# LCD.net
KiCad netlist of a schematic drawn in Altium Designer
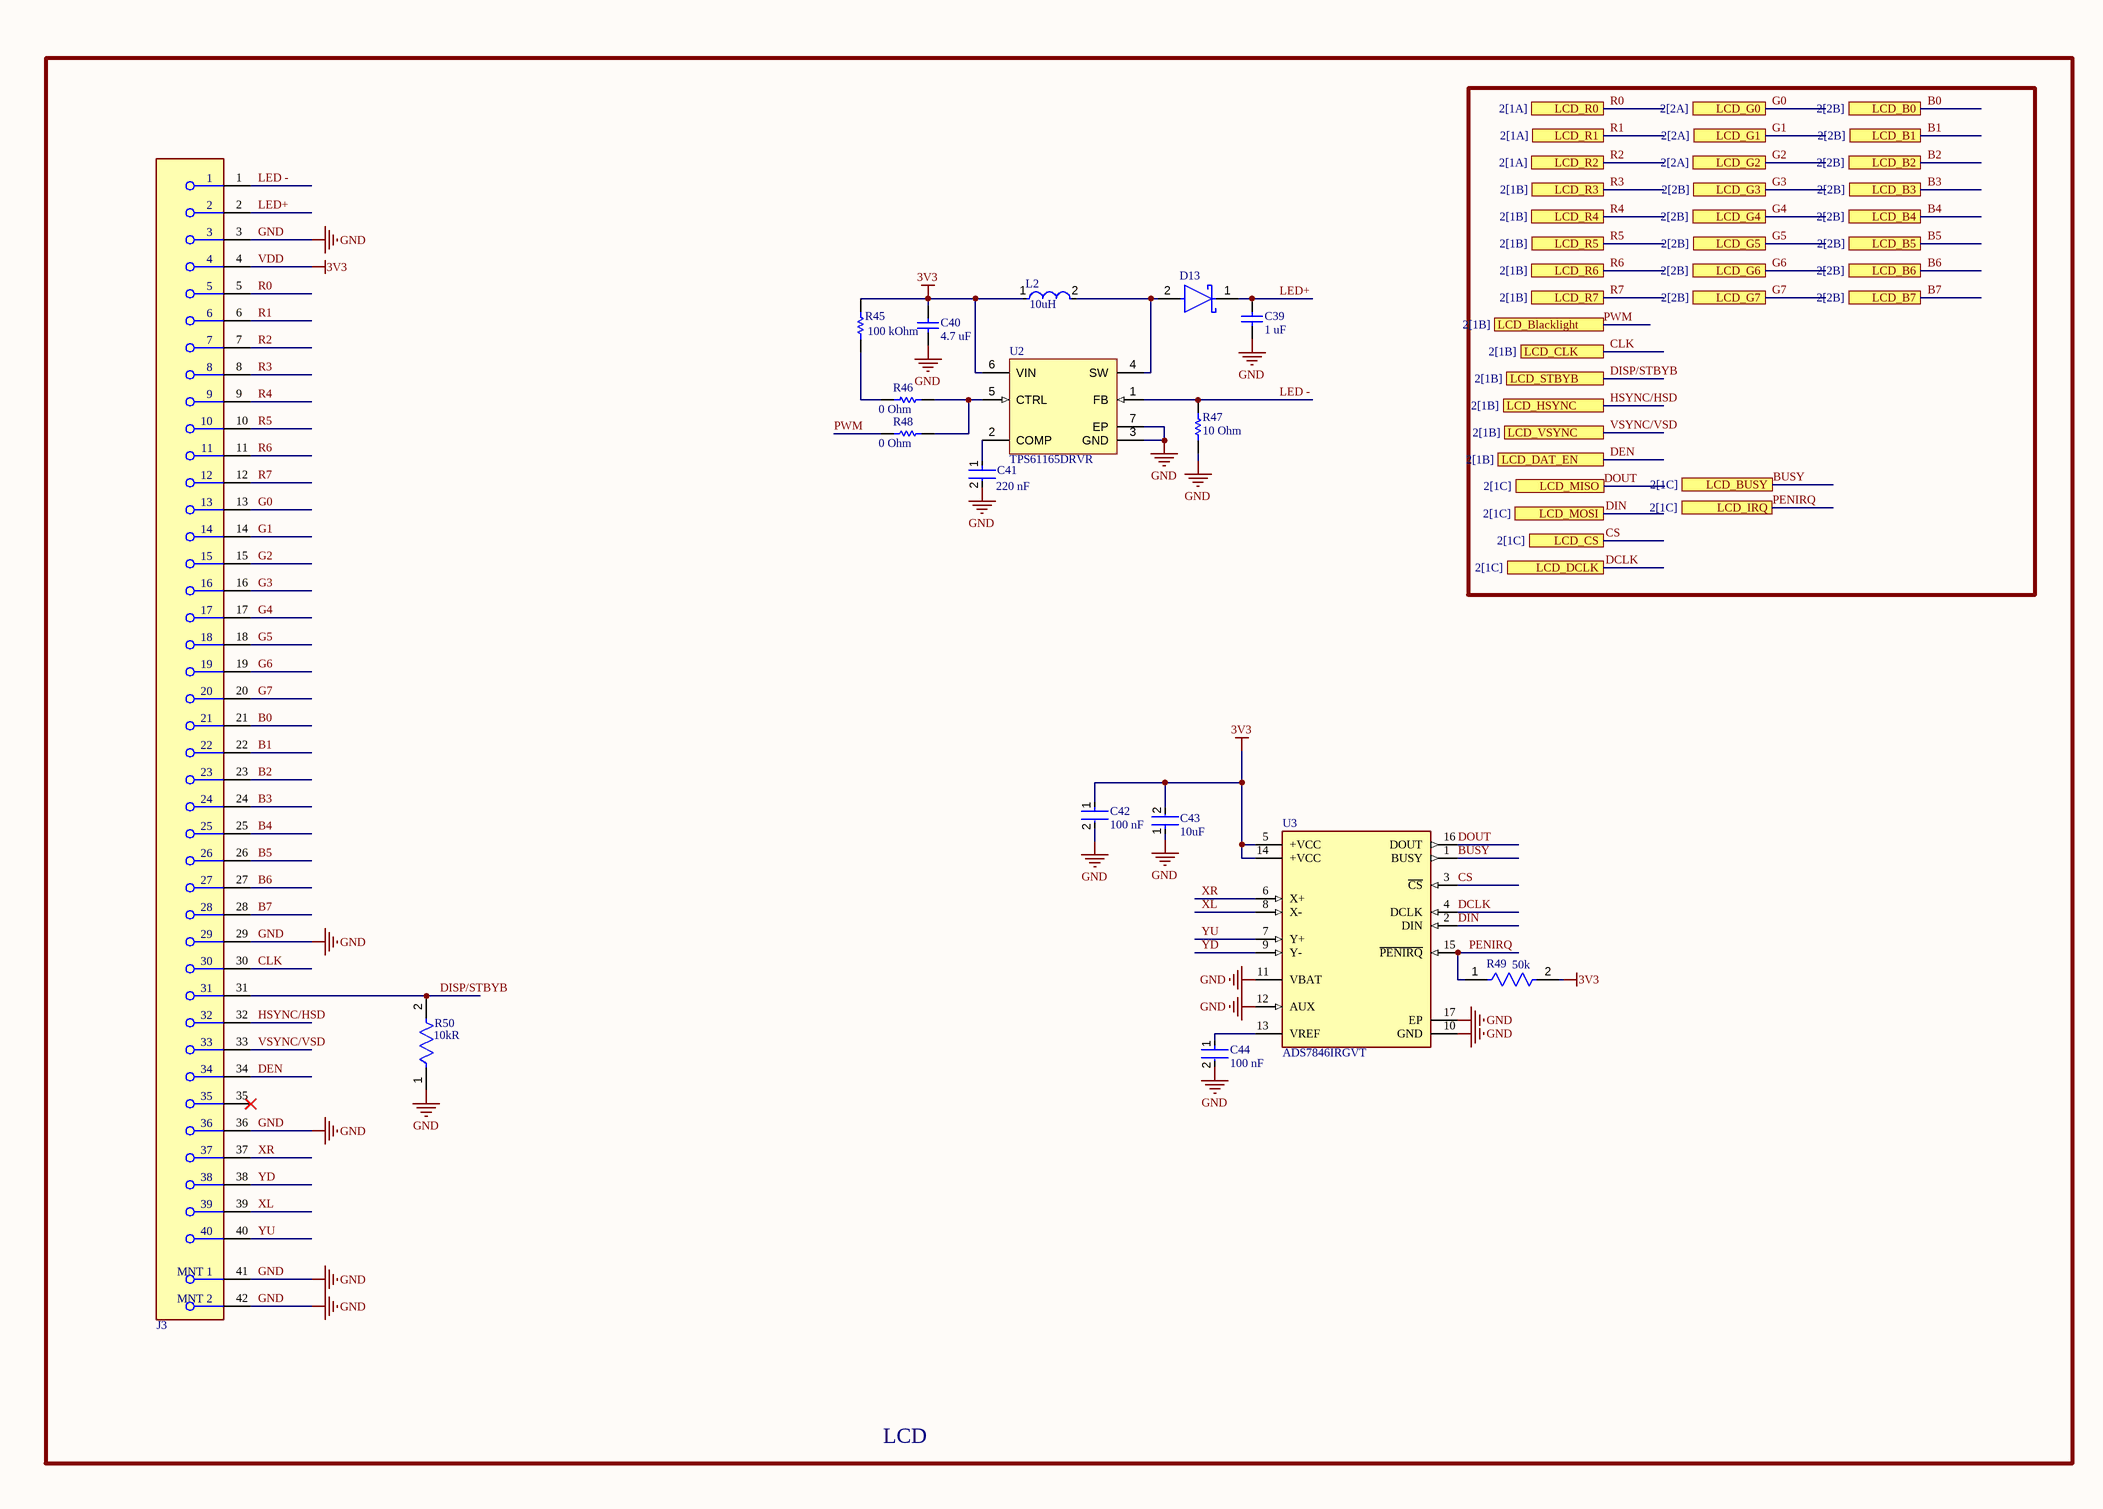
[diagram p0: LCD.SchDoc]

(export (version "E")
  (design (tool "Eeschema 10.0.6"))
  (components
    (comp (ref "C39")
      (value "1 uF")
      (footprint "CAPC2013X135X45LL10T25")
      (fields (field (name "PART NUMBER") "GRM21BR60J225KA01K") (field (name "MANUFACTURER") "Murata"))
      (libsource (lib "Altium Content Vault") (part "CAP"))
    )
    (comp (ref "C40")
      (value "4.7 uF")
      (footprint "CAPC2013X145X50NL20T25")
      (fields (field (name "PART NUMBER") "C0805C475K9PACTU") (field (name "MANUFACTURER") "Kemet"))
      (libsource (lib "Altium Content Vault") (part "CAP"))
    )
    (comp (ref "C41")
      (value "220 nF")
      (footprint "FP-CC0805-0_85-MFG")
      (description "CC0805 220 nF X7R 10.00% 16 V")
      (fields
        (field (name "MANUFACTURER") "Yageo")
        (field (name "OCTOPART") "https://octopart.com/cc0805kpx7r7bb224-yageo-24924096")
      )
      (libsource (lib "Altium Content Vault") (part "11868f565c42a9108669ba33697ecf6"))
    )
    (comp (ref "C42")
      (value "100 nF")
      (footprint "FP-CC0603-DA-MFG")
      (description "CAP CER 0.1UF 16V X7R 0603")
      (fields
        (field (name "OCTOPART") "https://octopart.com/cc0603krx7r7bb104-yageo-192941")
        (field (name "TOLERANCE") "0.1")
      )
      (libsource (lib "Altium Content Vault") (part "11868f565c42a9108669ba33697ecf6"))
    )
    (comp (ref "C43")
      (value "GRM21BR61E106MA73L")
      (footprint "FP-GRM21B-0_15-IPC_A")
      (description "Chip Multilayer Ceramic Capacitors for General Purpose, 0805, 10uF, X5R, 15%, 20%, 25V")
      (fields (field (name "TOLERANCE") "20%") (field (name "CAPACITANCE") "10uF"))
      (libsource (lib "Altium Content Vault") (part "b4654b650e69147ec39a6b967a45e02"))
    )
    (comp (ref "C44")
      (value "100 nF")
      (footprint "FP-CC0603-DA-MFG")
      (description "CAP CER 0.1UF 16V X7R 0603")
      (fields
        (field (name "OCTOPART") "https://octopart.com/cc0603krx7r7bb104-yageo-192941")
        (field (name "TOLERANCE") "0.1")
      )
      (libsource (lib "Altium Content Vault") (part "11868f565c42a9108669ba33697ecf6"))
    )
    (comp (ref "D13")
      (value "MBR0540-TP")
      (footprint "FP-SOD-123-MFG")
      (description "DIODE SCHOTTKY 40V 500MA SOD123")
      (libsource (lib "Altium Content Vault") (part "1d6ec82d83fb6aee721767c19dac4b9"))
    )
    (comp (ref "J3")
      (value "FH12-40S-0.5SH(55)")
      (footprint "FP-FH12-40S-0_5SH_55-MFG")
      (description "CONN FFC BOTTOM 40POS 0.50MM R/A")
      (libsource (lib "Altium Content Vault") (part "d90ebcb45eabe943beb5722ac69d035"))
    )
    (comp (ref "L2")
      (value "NR6012T100ME")
      (footprint "FP-NR6012-MFG")
      (description "SMD Power Inductors 10uH ±20% 1A 0.282Ω")
      (fields (field (name "INDUCTANCE") "10uH") (field (name "TOLERANCE") "20%"))
      (libsource (lib "Altium Content Vault") (part "725321dda6339637d4d059423bc1c3c"))
    )
    (comp (ref "R45")
      (value "100 kOhm")
      (footprint "RESC2013X70X40NL20T20")
      (fields (field (name "PART NUMBER") "ERJ-6GEYJ104V") (field (name "MANUFACTURER") "Panasonic"))
      (libsource (lib "Altium Content Vault") (part "RES"))
    )
    (comp (ref "R46")
      (value "0 Ohm")
      (footprint "RESC2013X50X30LL20T20")
      (fields (field (name "MANUFACTURER") "Vishay Dale") (field (name "PART NUMBER") "CRCW08050000Z0EA"))
      (libsource (lib "Altium Content Vault") (part "RES"))
    )
    (comp (ref "R47")
      (value "10 Ohm")
      (footprint "RESC2013X50X30NL20T20")
      (fields (field (name "MANUFACTURER") "Vishay Dale") (field (name "PART NUMBER") "CRCW080510R0FKEA"))
      (libsource (lib "Altium Content Vault") (part "RES"))
    )
    (comp (ref "R48")
      (value "0 Ohm")
      (footprint "RESC2013X50X30LL20T20")
      (fields (field (name "MANUFACTURER") "Vishay Dale") (field (name "PART NUMBER") "CRCW08050000Z0EA"))
      (libsource (lib "Altium Content Vault") (part "RES"))
    )
    (comp (ref "R49")
      (value "50k")
      (footprint "FP-RT0603-0_55-MFG")
      (description "RES 50K OHM 0.1% 1/10W 0603")
      (fields (field (name "Comment") "RT0603BRD0750KL"))
      (libsource (lib "Altium Content Vault") (part "1029c3af85768c4190bb7ad29bc67b5"))
    )
    (comp (ref "R50")
      (value "MC01W0805110K")
      (footprint "FP-MC01W0805-IPC_C")
      (description "Resistor, 10K, 0.1W, 1%, 0805, Reel")
      (fields (field (name "RESISTANCE") "10kR") (field (name "TOLERANCE") "1%"))
      (libsource (lib "Altium Content Vault") (part "1029c3af85768c4190bb7ad29bc67b5"))
    )
    (comp (ref "U2")
      (value "TPS61165DRVR")
      (footprint "DRV0006A_V")
      (fields (field (name "MANUFACTURER") "Texas Instruments"))
      (libsource (lib "Altium Content Vault") (part "TI-TPS6116XDRV6-1600X1000TP"))
    )
    (comp (ref "U3")
      (value "ADS7846IRGVT")
      (footprint "FP-RGV0016B-MFG")
      (description "IC SCREEN CNTRL 12BIT 16FN")
      (libsource (lib "Altium Content Vault") (part "e47298e896872d9f0e38206ef167a34"))
    )
  )
  (nets
    (net (code "1") (name "/B0") (class "Default")
      (node (ref "J3") (pin "21") (pinfunction "21_21") (pintype "passive"))
    )
    (net (code "2") (name "/B1") (class "Default")
      (node (ref "J3") (pin "22") (pinfunction "22_22") (pintype "passive"))
    )
    (net (code "3") (name "/B2") (class "Default")
      (node (ref "J3") (pin "23") (pinfunction "23_23") (pintype "passive"))
    )
    (net (code "4") (name "/B3") (class "Default")
      (node (ref "J3") (pin "24") (pinfunction "24_24") (pintype "passive"))
    )
    (net (code "5") (name "/B4") (class "Default")
      (node (ref "J3") (pin "25") (pinfunction "25_25") (pintype "passive"))
    )
    (net (code "6") (name "/B5") (class "Default")
      (node (ref "J3") (pin "26") (pinfunction "26_26") (pintype "passive"))
    )
    (net (code "7") (name "/B6") (class "Default")
      (node (ref "J3") (pin "27") (pinfunction "27_27") (pintype "passive"))
    )
    (net (code "8") (name "/B7") (class "Default")
      (node (ref "J3") (pin "28") (pinfunction "28_28") (pintype "passive"))
    )
    (net (code "9") (name "/BUSY") (class "Default")
      (node (ref "U3") (pin "1") (pinfunction "BUSY_1") (pintype "output"))
    )
    (net (code "10") (name "/CLK") (class "Default")
      (node (ref "J3") (pin "30") (pinfunction "30_30") (pintype "passive"))
    )
    (net (code "11") (name "/CS") (class "Default")
      (node (ref "U3") (pin "3") (pinfunction "~{CS}_3") (pintype "input"))
    )
    (net (code "12") (name "/DCLK") (class "Default")
      (node (ref "U3") (pin "4") (pinfunction "DCLK_4") (pintype "input"))
    )
    (net (code "13") (name "/DEN") (class "Default")
      (node (ref "J3") (pin "34") (pinfunction "34_34") (pintype "passive"))
    )
    (net (code "14") (name "/DIN") (class "Default")
      (node (ref "U3") (pin "2") (pinfunction "DIN_2") (pintype "input"))
    )
    (net (code "15") (name "/DISP{slash}STBYB") (class "Default")
      (node (ref "J3") (pin "31") (pinfunction "31_31") (pintype "passive"))
      (node (ref "R50") (pin "2") (pinfunction "2_2") (pintype "passive"))
    )
    (net (code "16") (name "/DOUT") (class "Default")
      (node (ref "U3") (pin "16") (pinfunction "DOUT_16") (pintype "output"))
    )
    (net (code "17") (name "/G0") (class "Default")
      (node (ref "J3") (pin "13") (pinfunction "13_13") (pintype "passive"))
    )
    (net (code "18") (name "/G1") (class "Default")
      (node (ref "J3") (pin "14") (pinfunction "14_14") (pintype "passive"))
    )
    (net (code "19") (name "/G2") (class "Default")
      (node (ref "J3") (pin "15") (pinfunction "15_15") (pintype "passive"))
    )
    (net (code "20") (name "/G3") (class "Default")
      (node (ref "J3") (pin "16") (pinfunction "16_16") (pintype "passive"))
    )
    (net (code "21") (name "/G4") (class "Default")
      (node (ref "J3") (pin "17") (pinfunction "17_17") (pintype "passive"))
    )
    (net (code "22") (name "/G5") (class "Default")
      (node (ref "J3") (pin "18") (pinfunction "18_18") (pintype "passive"))
    )
    (net (code "23") (name "/G6") (class "Default")
      (node (ref "J3") (pin "19") (pinfunction "19_19") (pintype "passive"))
    )
    (net (code "24") (name "/G7") (class "Default")
      (node (ref "J3") (pin "20") (pinfunction "20_20") (pintype "passive"))
    )
    (net (code "25") (name "/HSYNC{slash}HSD") (class "Default")
      (node (ref "J3") (pin "32") (pinfunction "32_32") (pintype "passive"))
    )
    (net (code "27") (name "/LED -") (class "Default")
      (node (ref "J3") (pin "1") (pinfunction "1_1") (pintype "passive"))
      (node (ref "R47") (pin "2") (pinfunction "2_2") (pintype "passive"))
      (node (ref "U2") (pin "1") (pinfunction "FB_1") (pintype "input"))
    )
    (net (code "28") (name "/LED+") (class "Default")
      (node (ref "C39") (pin "2") (pinfunction "2_2") (pintype "passive"))
      (node (ref "D13") (pin "1") (pinfunction "C_1") (pintype "passive"))
      (node (ref "J3") (pin "2") (pinfunction "2_2") (pintype "passive"))
    )
    (net (code "29") (name "/PENIRQ") (class "Default")
      (node (ref "R49") (pin "1") (pinfunction "1_1") (pintype "passive"))
      (node (ref "U3") (pin "15") (pinfunction "~{PENIRQ}_15") (pintype "input"))
    )
    (net (code "30") (name "/PWM") (class "Default")
      (node (ref "R48") (pin "1") (pinfunction "1_1") (pintype "passive"))
    )
    (net (code "31") (name "/R0") (class "Default")
      (node (ref "J3") (pin "5") (pinfunction "5_5") (pintype "passive"))
    )
    (net (code "32") (name "/R1") (class "Default")
      (node (ref "J3") (pin "6") (pinfunction "6_6") (pintype "passive"))
    )
    (net (code "33") (name "/R2") (class "Default")
      (node (ref "J3") (pin "7") (pinfunction "7_7") (pintype "passive"))
    )
    (net (code "34") (name "/R3") (class "Default")
      (node (ref "J3") (pin "8") (pinfunction "8_8") (pintype "passive"))
    )
    (net (code "35") (name "/R4") (class "Default")
      (node (ref "J3") (pin "9") (pinfunction "9_9") (pintype "passive"))
    )
    (net (code "36") (name "/R5") (class "Default")
      (node (ref "J3") (pin "10") (pinfunction "10_10") (pintype "passive"))
    )
    (net (code "37") (name "/R6") (class "Default")
      (node (ref "J3") (pin "11") (pinfunction "11_11") (pintype "passive"))
    )
    (net (code "38") (name "/R7") (class "Default")
      (node (ref "J3") (pin "12") (pinfunction "12_12") (pintype "passive"))
    )
    (net (code "39") (name "/VSYNC{slash}VSD") (class "Default")
      (node (ref "J3") (pin "33") (pinfunction "33_33") (pintype "passive"))
    )
    (net (code "40") (name "/XL") (class "Default")
      (node (ref "J3") (pin "39") (pinfunction "39_39") (pintype "passive"))
      (node (ref "U3") (pin "8") (pinfunction "X-_8") (pintype "input"))
    )
    (net (code "41") (name "/XR") (class "Default")
      (node (ref "J3") (pin "37") (pinfunction "37_37") (pintype "passive"))
      (node (ref "U3") (pin "6") (pinfunction "X+_6") (pintype "input"))
    )
    (net (code "42") (name "/YD") (class "Default")
      (node (ref "J3") (pin "38") (pinfunction "38_38") (pintype "passive"))
      (node (ref "U3") (pin "9") (pinfunction "Y-_9") (pintype "input"))
    )
    (net (code "43") (name "/YU") (class "Default")
      (node (ref "J3") (pin "40") (pinfunction "40_40") (pintype "passive"))
      (node (ref "U3") (pin "7") (pinfunction "Y+_7") (pintype "input"))
    )
    (net (code "44") (name "3V3") (class "Default")
      (node (ref "C40") (pin "2") (pinfunction "2_2") (pintype "passive"))
      (node (ref "C42") (pin "1") (pinfunction "1_1") (pintype "passive"))
      (node (ref "C43") (pin "2") (pinfunction "2_2") (pintype "passive"))
      (node (ref "J3") (pin "4") (pinfunction "4_4") (pintype "passive"))
      (node (ref "L2") (pin "1") (pinfunction "1_1") (pintype "passive"))
      (node (ref "R45") (pin "2") (pinfunction "2_2") (pintype "passive"))
      (node (ref "R49") (pin "2") (pinfunction "2_2") (pintype "passive"))
      (node (ref "U2") (pin "6") (pinfunction "VIN_6") (pintype "power_in"))
      (node (ref "U3") (pin "14") (pinfunction "+VCC_14") (pintype "power_in"))
      (node (ref "U3") (pin "5") (pinfunction "+VCC_5") (pintype "power_in"))
    )
    (net (code "45") (name "GND") (class "Default")
      (node (ref "C39") (pin "1") (pinfunction "1_1") (pintype "passive"))
      (node (ref "C40") (pin "1") (pinfunction "1_1") (pintype "passive"))
      (node (ref "C41") (pin "2") (pinfunction "2_2") (pintype "passive"))
      (node (ref "C42") (pin "2") (pinfunction "2_2") (pintype "passive"))
      (node (ref "C43") (pin "1") (pinfunction "1_1") (pintype "passive"))
      (node (ref "C44") (pin "2") (pinfunction "2_2") (pintype "passive"))
      (node (ref "J3") (pin "29") (pinfunction "29_29") (pintype "passive"))
      (node (ref "J3") (pin "3") (pinfunction "3_3") (pintype "passive"))
      (node (ref "J3") (pin "36") (pinfunction "36_36") (pintype "passive"))
      (node (ref "J3") (pin "41") (pinfunction "MNT_1_41") (pintype "passive"))
      (node (ref "J3") (pin "42") (pinfunction "MNT_2_42") (pintype "passive"))
      (node (ref "R47") (pin "1") (pinfunction "1_1") (pintype "passive"))
      (node (ref "R50") (pin "1") (pinfunction "1_1") (pintype "passive"))
      (node (ref "U2") (pin "3") (pinfunction "GND_3") (pintype "power_in"))
      (node (ref "U2") (pin "7") (pinfunction "EP_7") (pintype "power_in"))
      (node (ref "U3") (pin "10") (pinfunction "GND_10") (pintype "power_in"))
      (node (ref "U3") (pin "11") (pinfunction "VBAT_11") (pintype "power_in"))
      (node (ref "U3") (pin "12") (pinfunction "AUX_12") (pintype "input"))
      (node (ref "U3") (pin "17") (pinfunction "EP_17") (pintype "passive"))
    )
    (net (code "46") (name "Net-(D13-A)") (class "Default")
      (node (ref "D13") (pin "2") (pinfunction "A_2") (pintype "passive"))
      (node (ref "L2") (pin "2") (pinfunction "2_2") (pintype "passive"))
      (node (ref "U2") (pin "4") (pinfunction "SW_4") (pintype "power_in"))
    )
    (net (code "47") (name "Net-(R45-Pad1)") (class "Default")
      (node (ref "R45") (pin "1") (pinfunction "1_1") (pintype "passive"))
      (node (ref "R46") (pin "1") (pinfunction "1_1") (pintype "passive"))
    )
    (net (code "48") (name "Net-(U2-COMP)") (class "Default")
      (node (ref "C41") (pin "1") (pinfunction "1_1") (pintype "passive"))
      (node (ref "U2") (pin "2") (pinfunction "COMP_2") (pintype "passive"))
    )
    (net (code "49") (name "Net-(U2-CTRL)") (class "Default")
      (node (ref "R46") (pin "2") (pinfunction "2_2") (pintype "passive"))
      (node (ref "R48") (pin "2") (pinfunction "2_2") (pintype "passive"))
      (node (ref "U2") (pin "5") (pinfunction "CTRL_5") (pintype "input"))
    )
    (net (code "50") (name "Net-(U3-VREF)") (class "Default")
      (node (ref "C44") (pin "1") (pinfunction "1_1") (pintype "passive"))
      (node (ref "U3") (pin "13") (pinfunction "VREF_13") (pintype "passive"))
    )
    (net (code "51") (name "unconnected-(J3-Pad35)") (class "Default")
      (node (ref "J3") (pin "35") (pinfunction "35_35") (pintype "passive+no_connect"))
    )
  )
)
